# MdA_Power.net
KiCad netlist of a schematic drawn in Altium Designer
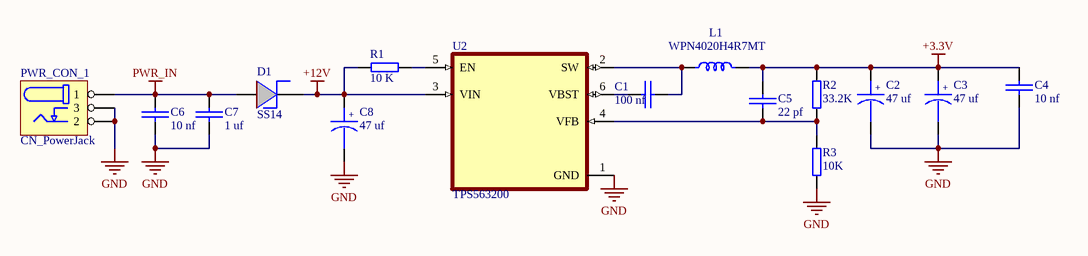
[diagram p0: MdA_Power.SchDoc]

(export (version "E")
  (design (tool "Eeschema 10.0.6"))
  (components
    (comp (ref "C1")
      (value "100 nf")
      (footprint "C_0402")
      (libsource (lib "Modulo de apertura") (part "CAP"))
    )
    (comp (ref "C2")
      (value "47 uf")
      (footprint "C_P_1210")
      (libsource (lib "Modulo de apertura") (part "CAP_P"))
    )
    (comp (ref "C3")
      (value "47 uf")
      (footprint "C_P_1210")
      (libsource (lib "Modulo de apertura") (part "CAP_P"))
    )
    (comp (ref "C4") (value "10 nf") (footprint "C_0603") (libsource (lib "Modulo de apertura") (part "CAP")))
    (comp (ref "C5") (value "22 pf") (footprint "C_0402") (libsource (lib "Modulo de apertura") (part "CAP")))
    (comp (ref "C6") (value "10 nf") (footprint "C_0402") (libsource (lib "Modulo de apertura") (part "CAP")))
    (comp (ref "C7") (value "1 uf") (footprint "C_0603") (libsource (lib "Modulo de apertura") (part "CAP")))
    (comp (ref "C8")
      (value "47 uf")
      (footprint "C_P_1210")
      (libsource (lib "Modulo de apertura") (part "CAP_P"))
    )
    (comp (ref "D1")
      (value "SS14")
      (footprint "D_SMA")
      (libsource (lib "Modulo de apertura") (part "DIODE_SH"))
    )
    (comp (ref "L1")
      (value "WPN4020H4R7MT")
      (footprint "IFSC1515AH")
      (libsource (lib "Modulo de apertura") (part "IND"))
    )
    (comp (ref "PWR_CON_1")
      (value "CN_PowerJack")
      (footprint "PJ002B")
      (libsource (lib "Modulo de apertura") (part "CN_PowerJack"))
    )
    (comp (ref "R1") (value "10 K") (footprint "R_0402") (libsource (lib "Modulo de apertura") (part "RES")))
    (comp (ref "R2") (value "33.2K") (footprint "R_0402") (libsource (lib "Modulo de apertura") (part "RES")))
    (comp (ref "R3") (value "10K") (footprint "R_0402") (libsource (lib "Modulo de apertura") (part "RES")))
    (comp (ref "U2")
      (value "TPS563200")
      (footprint "SOT-23-6")
      (libsource (lib "Modulo de apertura") (part "TPS563200"))
    )
  )
  (nets
    (net (code "1") (name "+3.3V") (class "Default")
      (node (ref "C2") (pin "1") (pinfunction "1_1") (pintype "passive"))
      (node (ref "C3") (pin "1") (pinfunction "1_1") (pintype "passive"))
      (node (ref "C4") (pin "2") (pinfunction "2_2") (pintype "passive"))
      (node (ref "C5") (pin "1") (pinfunction "1_1") (pintype "passive"))
      (node (ref "L1") (pin "2") (pinfunction "2_2") (pintype "passive"))
      (node (ref "R2") (pin "2") (pinfunction "2_2") (pintype "passive"))
    )
    (net (code "2") (name "+12V") (class "Default")
      (node (ref "C8") (pin "1") (pinfunction "1_1") (pintype "passive"))
      (node (ref "D1") (pin "2") (pinfunction "K_2") (pintype "passive"))
      (node (ref "R1") (pin "2") (pinfunction "2_2") (pintype "passive"))
      (node (ref "U2") (pin "3") (pinfunction "VIN_3") (pintype "input"))
    )
    (net (code "3") (name "GND") (class "Default")
      (node (ref "C2") (pin "2") (pinfunction "2_2") (pintype "passive"))
      (node (ref "C3") (pin "2") (pinfunction "2_2") (pintype "passive"))
      (node (ref "C4") (pin "1") (pinfunction "1_1") (pintype "passive"))
      (node (ref "C6") (pin "2") (pinfunction "2_2") (pintype "passive"))
      (node (ref "C7") (pin "2") (pinfunction "2_2") (pintype "passive"))
      (node (ref "C8") (pin "2") (pinfunction "2_2") (pintype "passive"))
      (node (ref "PWR_CON_1") (pin "2") (pinfunction "2_2") (pintype "passive"))
      (node (ref "PWR_CON_1") (pin "3") (pinfunction "3_3") (pintype "passive"))
      (node (ref "R3") (pin "1") (pinfunction "1_1") (pintype "passive"))
      (node (ref "U2") (pin "1") (pinfunction "GND_1") (pintype "power_in"))
    )
    (net (code "4") (name "Net-(U2-EN)") (class "Default")
      (node (ref "R1") (pin "1") (pinfunction "1_1") (pintype "passive"))
      (node (ref "U2") (pin "5") (pinfunction "EN_5") (pintype "input"))
    )
    (net (code "5") (name "Net-(U2-SW)") (class "Default")
      (node (ref "C1") (pin "2") (pinfunction "2_2") (pintype "passive"))
      (node (ref "L1") (pin "1") (pinfunction "1_1") (pintype "passive"))
      (node (ref "U2") (pin "2") (pinfunction "SW_2") (pintype "bidirectional"))
    )
    (net (code "6") (name "Net-(U2-VBST)") (class "Default")
      (node (ref "C1") (pin "1") (pinfunction "1_1") (pintype "passive"))
      (node (ref "U2") (pin "6") (pinfunction "VBST_6") (pintype "bidirectional"))
    )
    (net (code "7") (name "Net-(U2-VFB)") (class "Default")
      (node (ref "C5") (pin "2") (pinfunction "2_2") (pintype "passive"))
      (node (ref "R2") (pin "1") (pinfunction "1_1") (pintype "passive"))
      (node (ref "R3") (pin "2") (pinfunction "2_2") (pintype "passive"))
      (node (ref "U2") (pin "4") (pinfunction "VFB_4") (pintype "input"))
    )
    (net (code "8") (name "PWR_IN") (class "Default")
      (node (ref "C6") (pin "1") (pinfunction "1_1") (pintype "passive"))
      (node (ref "C7") (pin "1") (pinfunction "1_1") (pintype "passive"))
      (node (ref "D1") (pin "1") (pinfunction "A_1") (pintype "passive"))
      (node (ref "PWR_CON_1") (pin "1") (pinfunction "1_1") (pintype "passive"))
    )
  )
)
